# H10R7_Frontend_1.net
KiCad netlist of a schematic drawn in Altium Designer
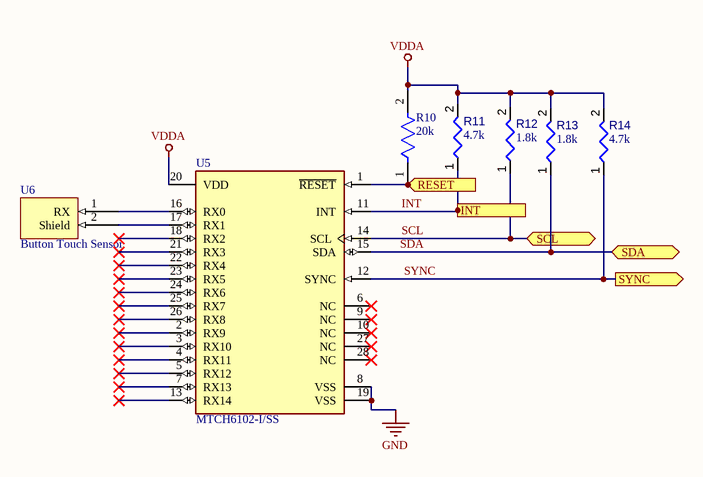
[diagram p0: H10R7_Frontend 1.SchDoc]

(export (version "E")
  (design (tool "Eeschema 10.0.6"))
  (components
    (comp (ref "R10")
      (value "20k")
      (footprint "FP-AC0603-IPC_C")
      (description "Res Thick Film 0603 20K Ohm 5% 0.1W(1/10W) ±100ppm/C Pad SMD T/R Automotive AEC-Q200")
      (fields (field (name "TOLERANCE") "5%") (field (name "Comment") "AC0603JR-0720KL"))
      (libsource (lib "Luan's Altium 365") (part "1029c3af85768c4190bb7ad29bc67b5"))
    )
    (comp (ref "R11")
      (value "4.7k")
      (footprint "RESC1608X55X25ML10T15")
      (description "Chip Resistor, 4.7 KOhm, +/- 1%, 0.1 W, -55 to 155 degC, 0603 (1608 Metric)")
      (fields (field (name "TOLERANCE") "1%") (field (name "POWER") "100mW"))
      (libsource (lib "Luan's Altium 365") (part "RES-2"))
    )
    (comp (ref "R12")
      (value "1.8k")
      (footprint "FP-RMCF0603-MFG")
      (description "Res Thick Film 0603 1.8K Ohm 5% 1/10W ±200ppm/°C Molded SMD Paper T/R")
      (fields (field (name "TOLERANCE") "5%") (field (name "Comment") "RMCF0603JG1K80"))
      (libsource (lib "Luan's Altium 365") (part "RES-2"))
    )
    (comp (ref "R13")
      (value "1.8k")
      (footprint "FP-RMCF0603-MFG")
      (description "Res Thick Film 0603 1.8K Ohm 5% 1/10W ±200ppm/°C Molded SMD Paper T/R")
      (fields (field (name "TOLERANCE") "5%") (field (name "Comment") "RMCF0603JG1K80"))
      (libsource (lib "Luan's Altium 365") (part "RES-2"))
    )
    (comp (ref "R14")
      (value "4.7k")
      (footprint "RESC1608X55X25ML10T15")
      (description "Chip Resistor, 4.7 KOhm, +/- 1%, 0.1 W, -55 to 155 degC, 0603 (1608 Metric)")
      (fields (field (name "TOLERANCE") "1%") (field (name "POWER") "100mW"))
      (libsource (lib "Luan's Altium 365") (part "RES-2"))
    )
    (comp (ref "U5")
      (value "MTCH6102-I/SS")
      (footprint "FP-C04-073-IPC_A")
      (description "Sensor Controller Capacitive 15-Ch Serial I2C 28-Pin SSOP Tube")
      (libsource (lib "Luan's Altium 365") (part "17f10156cec23822e09dc8753f2acd0"))
    )
    (comp (ref "U6")
      (value "Button Touch Sensor")
      (footprint "Button Touch Sensor")
      (description "1 button touch sensor with shield")
      (libsource (lib "Luan's Altium 365") (part "Button Touch Sensor"))
    )
  )
  (nets
    (net (code "1") (name "/INT") (class "Default")
      (node (ref "R11") (pin "1") (pinfunction "1_1") (pintype "passive"))
      (node (ref "U5") (pin "11") (pinfunction "INT_11") (pintype "input"))
    )
    (net (code "2") (name "/RESET") (class "Default")
      (node (ref "R10") (pin "1") (pinfunction "1_1") (pintype "passive"))
      (node (ref "U5") (pin "1") (pinfunction "~{RESET}_1") (pintype "input"))
    )
    (net (code "3") (name "/SCL") (class "Default")
      (node (ref "R12") (pin "1") (pinfunction "1_1") (pintype "passive"))
      (node (ref "U5") (pin "14") (pinfunction "SCL_14") (pintype "input"))
    )
    (net (code "4") (name "/SDA") (class "Default")
      (node (ref "R13") (pin "1") (pinfunction "1_1") (pintype "passive"))
      (node (ref "U5") (pin "15") (pinfunction "SDA_15") (pintype "bidirectional"))
    )
    (net (code "5") (name "/SYNC") (class "Default")
      (node (ref "R14") (pin "1") (pinfunction "1_1") (pintype "passive"))
      (node (ref "U5") (pin "12") (pinfunction "SYNC_12") (pintype "input"))
    )
    (net (code "6") (name "GND") (class "Default")
      (node (ref "U5") (pin "19") (pinfunction "VSS_19") (pintype "power_in"))
      (node (ref "U5") (pin "8") (pinfunction "VSS_8") (pintype "power_in"))
    )
    (net (code "7") (name "Net-(U5-RX0)") (class "Default")
      (node (ref "U5") (pin "16") (pinfunction "RX0_16") (pintype "bidirectional"))
      (node (ref "U6") (pin "1") (pinfunction "RX_1") (pintype "input"))
    )
    (net (code "8") (name "Net-(U5-RX1)") (class "Default")
      (node (ref "U5") (pin "17") (pinfunction "RX1_17") (pintype "bidirectional"))
      (node (ref "U6") (pin "2") (pinfunction "Shield_2") (pintype "input"))
    )
    (net (code "9") (name "VDDA") (class "Default")
      (node (ref "R10") (pin "2") (pinfunction "2_2") (pintype "passive"))
      (node (ref "R11") (pin "2") (pinfunction "2_2") (pintype "passive"))
      (node (ref "R12") (pin "2") (pinfunction "2_2") (pintype "passive"))
      (node (ref "R13") (pin "2") (pinfunction "2_2") (pintype "passive"))
      (node (ref "R14") (pin "2") (pinfunction "2_2") (pintype "passive"))
      (node (ref "U5") (pin "20") (pinfunction "VDD_20") (pintype "power_in"))
    )
    (net (code "10") (name "unconnected-(U5-NC-Pad6)") (class "Default")
      (node (ref "U5") (pin "6") (pinfunction "NC_6") (pintype "passive+no_connect"))
    )
    (net (code "11") (name "unconnected-(U5-NC-Pad9)") (class "Default")
      (node (ref "U5") (pin "9") (pinfunction "NC_9") (pintype "passive+no_connect"))
    )
    (net (code "12") (name "unconnected-(U5-NC-Pad10)") (class "Default")
      (node (ref "U5") (pin "10") (pinfunction "NC_10") (pintype "passive+no_connect"))
    )
    (net (code "13") (name "unconnected-(U5-NC-Pad27)") (class "Default")
      (node (ref "U5") (pin "27") (pinfunction "NC_27") (pintype "passive+no_connect"))
    )
    (net (code "14") (name "unconnected-(U5-NC-Pad28)") (class "Default")
      (node (ref "U5") (pin "28") (pinfunction "NC_28") (pintype "passive+no_connect"))
    )
    (net (code "15") (name "unconnected-(U5-RX2-Pad18)") (class "Default")
      (node (ref "U5") (pin "18") (pinfunction "RX2_18") (pintype "bidirectional+no_connect"))
    )
    (net (code "16") (name "unconnected-(U5-RX3-Pad21)") (class "Default")
      (node (ref "U5") (pin "21") (pinfunction "RX3_21") (pintype "bidirectional+no_connect"))
    )
    (net (code "17") (name "unconnected-(U5-RX4-Pad22)") (class "Default")
      (node (ref "U5") (pin "22") (pinfunction "RX4_22") (pintype "bidirectional+no_connect"))
    )
    (net (code "18") (name "unconnected-(U5-RX5-Pad23)") (class "Default")
      (node (ref "U5") (pin "23") (pinfunction "RX5_23") (pintype "bidirectional+no_connect"))
    )
    (net (code "19") (name "unconnected-(U5-RX6-Pad24)") (class "Default")
      (node (ref "U5") (pin "24") (pinfunction "RX6_24") (pintype "bidirectional+no_connect"))
    )
    (net (code "20") (name "unconnected-(U5-RX7-Pad25)") (class "Default")
      (node (ref "U5") (pin "25") (pinfunction "RX7_25") (pintype "bidirectional+no_connect"))
    )
    (net (code "21") (name "unconnected-(U5-RX8-Pad26)") (class "Default")
      (node (ref "U5") (pin "26") (pinfunction "RX8_26") (pintype "bidirectional+no_connect"))
    )
    (net (code "22") (name "unconnected-(U5-RX9-Pad2)") (class "Default")
      (node (ref "U5") (pin "2") (pinfunction "RX9_2") (pintype "bidirectional+no_connect"))
    )
    (net (code "23") (name "unconnected-(U5-RX10-Pad3)") (class "Default")
      (node (ref "U5") (pin "3") (pinfunction "RX10_3") (pintype "bidirectional+no_connect"))
    )
    (net (code "24") (name "unconnected-(U5-RX11-Pad4)") (class "Default")
      (node (ref "U5") (pin "4") (pinfunction "RX11_4") (pintype "bidirectional+no_connect"))
    )
    (net (code "25") (name "unconnected-(U5-RX12-Pad5)") (class "Default")
      (node (ref "U5") (pin "5") (pinfunction "RX12_5") (pintype "bidirectional+no_connect"))
    )
    (net (code "26") (name "unconnected-(U5-RX13-Pad7)") (class "Default")
      (node (ref "U5") (pin "7") (pinfunction "RX13_7") (pintype "bidirectional+no_connect"))
    )
    (net (code "27") (name "unconnected-(U5-RX14-Pad13)") (class "Default")
      (node (ref "U5") (pin "13") (pinfunction "RX14_13") (pintype "bidirectional+no_connect"))
    )
  )
)
